# design.net
KiCad netlist of a schematic drawn in Altium Designer
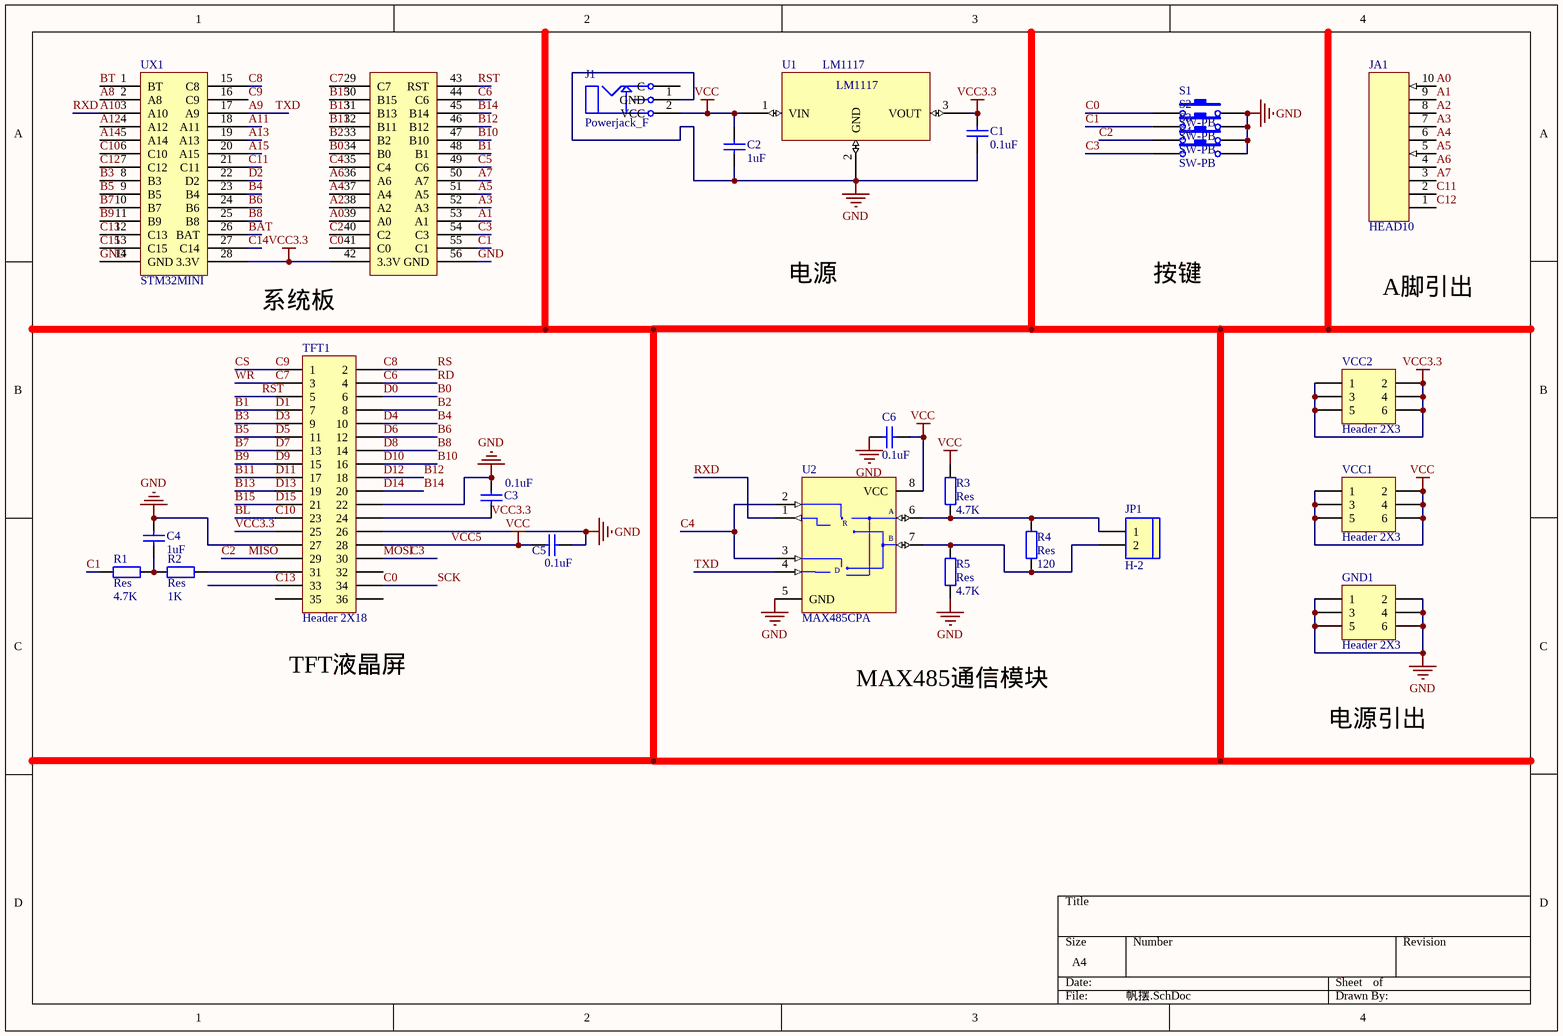
[diagram p0: 帆摆.SchDoc]

(export (version "E")
  (design (tool "Eeschema 10.0.6"))
  (components
    (comp (ref "C1")
      (value "0.1uF")
      (footprint "CC1005-0402")
      (description "Capacitor")
      (fields
        (field (name "MANUFACTURER") "Generic Components")
        (field (name "Comment") "CAP")
        (field (name "PUBLISHER") "Altium Hobart Technology Centre")
      )
      (libsource (lib "HGH") (part "CAP"))
    )
    (comp (ref "C2")
      (value "1uF")
      (footprint "CC1005-0402")
      (description "Capacitor")
      (fields
        (field (name "MANUFACTURER") "Generic Components")
        (field (name "Comment") "CAP")
        (field (name "PUBLISHER") "Altium Hobart Technology Centre")
      )
      (libsource (lib "HGH") (part "CAP"))
    )
    (comp (ref "C3")
      (value "0.1uF")
      (footprint "CC1005-0402")
      (description "Capacitor")
      (fields
        (field (name "MANUFACTURER") "Generic Components")
        (field (name "Comment") "CAP")
        (field (name "PUBLISHER") "Altium Hobart Technology Centre")
      )
      (libsource (lib "HGH - 副本") (part "CAP"))
    )
    (comp (ref "C4")
      (value "1uF")
      (footprint "CC1005-0402")
      (description "Capacitor")
      (fields
        (field (name "MANUFACTURER") "Generic Components")
        (field (name "Comment") "CAP")
        (field (name "PUBLISHER") "Altium Hobart Technology Centre")
      )
      (libsource (lib "HGH - 副本") (part "CAP"))
    )
    (comp (ref "C5")
      (value "0.1uF")
      (footprint "CC1005-0402")
      (description "Capacitor")
      (fields
        (field (name "MANUFACTURER") "Generic Components")
        (field (name "Comment") "CAP")
        (field (name "PUBLISHER") "Altium Hobart Technology Centre")
      )
      (libsource (lib "HGH - 副本") (part "CAP"))
    )
    (comp (ref "C6")
      (value "0.1uF")
      (footprint "CC1005-0402")
      (description "Capacitor")
      (fields
        (field (name "MANUFACTURER") "Generic Components")
        (field (name "Comment") "CAP")
        (field (name "PUBLISHER") "Altium Hobart Technology Centre")
      )
      (libsource (lib "HGH") (part "CAP"))
    )
    (comp (ref "GND1")
      (value "Header 2X3")
      (footprint "HDR2-3")
      (description "Header, 3-Pin, Dual row")
      (fields (field (name "MANUFACTURER") "Generic Components"))
      (libsource (lib "HGH") (part "Header 2X3"))
    )
    (comp (ref "J1")
      (value "Powerjack_F")
      (footprint "PWJ-2/3")
      (description "2-Conductor Jack with 1 break contact")
      (fields (field (name "MANUFACTURER") "Generic Components"))
      (libsource (lib "HGH") (part "Powerjack_F"))
    )
    (comp (ref "JA1")
      (value "HEAD10")
      (footprint "HEAD10M")
      (description "Connector,10-pin")
      (libsource (lib "HGH") (part "HEAD10"))
    )
    (comp (ref "JP1")
      (value "H-2")
      (footprint "H-2/2-T")
      (description "Header, 2-Pin")
      (fields (field (name "MANUFACTURER") "Generic Components"))
      (libsource (lib "HGH") (part "H-2"))
    )
    (comp (ref "R1")
      (value "Res")
      (footprint "R2012-0805")
      (description "Resistor")
      (fields
        (field (name "MANUFACTURER") "Generic Components")
        (field (name "ALTIUM_VALUE") "4.7K")
        (field (name "PUBLISHER") "Altium Hobart Technology Centre")
      )
      (libsource (lib "HGH - 副本") (part "Res"))
    )
    (comp (ref "R2")
      (value "Res")
      (footprint "R2012-0805")
      (description "Resistor")
      (fields
        (field (name "MANUFACTURER") "Generic Components")
        (field (name "ALTIUM_VALUE") "1K")
        (field (name "PUBLISHER") "Altium Hobart Technology Centre")
      )
      (libsource (lib "HGH - 副本") (part "Res"))
    )
    (comp (ref "R3")
      (value "Res")
      (footprint "R2012-0805")
      (description "Resistor")
      (fields
        (field (name "MANUFACTURER") "Generic Components")
        (field (name "ALTIUM_VALUE") "4.7K")
        (field (name "PUBLISHER") "Altium Hobart Technology Centre")
      )
      (libsource (lib "HGH") (part "Res"))
    )
    (comp (ref "R4")
      (value "Res")
      (footprint "R2012-0805")
      (description "Resistor")
      (fields
        (field (name "MANUFACTURER") "Generic Components")
        (field (name "ALTIUM_VALUE") "120")
        (field (name "PUBLISHER") "Altium Hobart Technology Centre")
      )
      (libsource (lib "HGH") (part "Res"))
    )
    (comp (ref "R5")
      (value "Res")
      (footprint "R2012-0805")
      (description "Resistor")
      (fields
        (field (name "MANUFACTURER") "Generic Components")
        (field (name "ALTIUM_VALUE") "4.7K")
        (field (name "PUBLISHER") "Altium Hobart Technology Centre")
      )
      (libsource (lib "HGH") (part "Res"))
    )
    (comp (ref "S1")
      (value "SW-PB")
      (footprint "SW-PB-4S")
      (description "Switch")
      (fields (field (name "MANUFACTURER") "Generic Components"))
      (libsource (lib "实验室") (part "SW-PB"))
    )
    (comp (ref "S2")
      (value "SW-PB")
      (footprint "SW-PB-4S")
      (description "Switch")
      (fields (field (name "MANUFACTURER") "Generic Components"))
      (libsource (lib "实验室") (part "SW-PB"))
    )
    (comp (ref "S3")
      (value "SW-PB")
      (footprint "SW-PB-4S")
      (description "Switch")
      (fields (field (name "MANUFACTURER") "Generic Components"))
      (libsource (lib "实验室") (part "SW-PB"))
    )
    (comp (ref "S4")
      (value "SW-PB")
      (footprint "SW-PB-4S")
      (description "Switch")
      (fields (field (name "MANUFACTURER") "Generic Components"))
      (libsource (lib "实验室") (part "SW-PB"))
    )
    (comp (ref "TFT1")
      (value "Header 2X18")
      (footprint "HDR2-18")
      (description "Header, 18Pin, Dual row")
      (fields (field (name "MANUFACTURER") "Generic Components"))
      (libsource (lib "HGH - 副本") (part "Header 2X18"))
    )
    (comp (ref "U1") (value "LM1117") (footprint "DSO-G3/P2.3") (libsource (lib "HGH") (part "LM1117")))
    (comp (ref "U2")
      (value "MAX485CPA")
      (footprint "DIP8")
      (description "Low-Power, Slew-Rate-Limited RS-485/RS-422 Transceiver")
      (fields
        (field (name "MANUFACTURER") "Maxim")
        (field (name "PUBLISHER") "Altium Hobart Technology Centre")
      )
      (libsource (lib "HGH") (part "MAX485CPA"))
    )
    (comp (ref "UX1")
      (value "STM32MINI")
      (footprint "STM32---MIN---64")
      (libsource (lib "HGH") (part "STM32---MIN--64"))
    )
    (comp (ref "VCC1")
      (value "Header 2X3")
      (footprint "HDR2-3")
      (description "Header, 3-Pin, Dual row")
      (fields (field (name "MANUFACTURER") "Generic Components"))
      (libsource (lib "HGH") (part "Header 2X3"))
    )
    (comp (ref "VCC2")
      (value "Header 2X3")
      (footprint "HDR2-3")
      (description "Header, 3-Pin, Dual row")
      (fields (field (name "MANUFACTURER") "Generic Components"))
      (libsource (lib "HGH") (part "Header 2X3"))
    )
  )
  (nets
    (net (code "2") (name "/A0") (class "Default")
      (node (ref "JA1") (pin "10") (pinfunction "10_10") (pintype "input"))
      (node (ref "UX1") (pin "39") (pinfunction "A0_39") (pintype "passive"))
    )
    (net (code "3") (name "/A1") (class "Default")
      (node (ref "JA1") (pin "9") (pinfunction "9_9") (pintype "passive"))
      (node (ref "UX1") (pin "53") (pinfunction "A1_53") (pintype "passive"))
    )
    (net (code "4") (name "/A2") (class "Default")
      (node (ref "JA1") (pin "8") (pinfunction "8_8") (pintype "passive"))
      (node (ref "UX1") (pin "38") (pinfunction "A2_38") (pintype "passive"))
    )
    (net (code "5") (name "/A3") (class "Default")
      (node (ref "JA1") (pin "7") (pinfunction "7_7") (pintype "passive"))
      (node (ref "UX1") (pin "52") (pinfunction "A3_52") (pintype "passive"))
    )
    (net (code "6") (name "/A4") (class "Default")
      (node (ref "JA1") (pin "6") (pinfunction "6_6") (pintype "passive"))
      (node (ref "UX1") (pin "37") (pinfunction "A4_37") (pintype "passive"))
    )
    (net (code "7") (name "/A5") (class "Default")
      (node (ref "JA1") (pin "5") (pinfunction "5_5") (pintype "input"))
      (node (ref "UX1") (pin "51") (pinfunction "A5_51") (pintype "passive"))
    )
    (net (code "8") (name "/A6") (class "Default")
      (node (ref "JA1") (pin "4") (pinfunction "4_4") (pintype "power_in"))
      (node (ref "UX1") (pin "36") (pinfunction "A6_36") (pintype "passive"))
    )
    (net (code "9") (name "/A7") (class "Default")
      (node (ref "JA1") (pin "3") (pinfunction "3_3") (pintype "power_in"))
      (node (ref "UX1") (pin "50") (pinfunction "A7_50") (pintype "passive"))
    )
    (net (code "10") (name "/A8") (class "Default")
      (node (ref "UX1") (pin "2") (pinfunction "A8_2") (pintype "passive"))
    )
    (net (code "11") (name "/A9") (class "Default")
      (node (ref "U2") (pin "4") (pinfunction "DI_4") (pintype "input"))
      (node (ref "UX1") (pin "17") (pinfunction "A9_17") (pintype "passive"))
    )
    (net (code "12") (name "/A10") (class "Default")
      (node (ref "U2") (pin "1") (pinfunction "RO_1") (pintype "output"))
      (node (ref "UX1") (pin "3") (pinfunction "A10_3") (pintype "passive"))
    )
    (net (code "13") (name "/A11") (class "Default")
      (node (ref "UX1") (pin "18") (pinfunction "A11_18") (pintype "passive"))
    )
    (net (code "14") (name "/A12") (class "Default")
      (node (ref "UX1") (pin "4") (pinfunction "A12_4") (pintype "passive"))
    )
    (net (code "15") (name "/A13") (class "Default")
      (node (ref "UX1") (pin "19") (pinfunction "A13_19") (pintype "passive"))
    )
    (net (code "16") (name "/A14") (class "Default")
      (node (ref "UX1") (pin "5") (pinfunction "A14_5") (pintype "passive"))
    )
    (net (code "17") (name "/A15") (class "Default")
      (node (ref "UX1") (pin "20") (pinfunction "A15_20") (pintype "passive"))
    )
    (net (code "20") (name "/B0") (class "Default")
      (node (ref "TFT1") (pin "6") (pinfunction "6_6") (pintype "passive"))
      (node (ref "UX1") (pin "34") (pinfunction "B0_34") (pintype "passive"))
    )
    (net (code "21") (name "/B1") (class "Default")
      (node (ref "TFT1") (pin "7") (pinfunction "7_7") (pintype "passive"))
      (node (ref "UX1") (pin "48") (pinfunction "B1_48") (pintype "passive"))
    )
    (net (code "22") (name "/B2") (class "Default")
      (node (ref "TFT1") (pin "8") (pinfunction "8_8") (pintype "passive"))
      (node (ref "UX1") (pin "33") (pinfunction "B2_33") (pintype "passive"))
    )
    (net (code "23") (name "/B3") (class "Default")
      (node (ref "TFT1") (pin "9") (pinfunction "9_9") (pintype "passive"))
      (node (ref "UX1") (pin "8") (pinfunction "B3_8") (pintype "passive"))
    )
    (net (code "24") (name "/B4") (class "Default")
      (node (ref "TFT1") (pin "10") (pinfunction "10_10") (pintype "passive"))
      (node (ref "UX1") (pin "23") (pinfunction "B4_23") (pintype "passive"))
    )
    (net (code "25") (name "/B5") (class "Default")
      (node (ref "TFT1") (pin "11") (pinfunction "11_11") (pintype "passive"))
      (node (ref "UX1") (pin "9") (pinfunction "B5_9") (pintype "passive"))
    )
    (net (code "26") (name "/B6") (class "Default")
      (node (ref "TFT1") (pin "12") (pinfunction "12_12") (pintype "passive"))
      (node (ref "UX1") (pin "24") (pinfunction "B6_24") (pintype "passive"))
    )
    (net (code "27") (name "/B7") (class "Default")
      (node (ref "TFT1") (pin "13") (pinfunction "13_13") (pintype "passive"))
      (node (ref "UX1") (pin "10") (pinfunction "B7_10") (pintype "passive"))
    )
    (net (code "28") (name "/B8") (class "Default")
      (node (ref "TFT1") (pin "14") (pinfunction "14_14") (pintype "passive"))
      (node (ref "UX1") (pin "25") (pinfunction "B8_25") (pintype "passive"))
    )
    (net (code "29") (name "/B9") (class "Default")
      (node (ref "TFT1") (pin "15") (pinfunction "15_15") (pintype "passive"))
      (node (ref "UX1") (pin "11") (pinfunction "B9_11") (pintype "passive"))
    )
    (net (code "30") (name "/B10") (class "Default")
      (node (ref "TFT1") (pin "16") (pinfunction "16_16") (pintype "passive"))
      (node (ref "UX1") (pin "47") (pinfunction "B10_47") (pintype "passive"))
    )
    (net (code "31") (name "/B11") (class "Default")
      (node (ref "TFT1") (pin "17") (pinfunction "17_17") (pintype "passive"))
      (node (ref "UX1") (pin "32") (pinfunction "B11_32") (pintype "passive"))
    )
    (net (code "32") (name "/B12") (class "Default")
      (node (ref "TFT1") (pin "18") (pinfunction "18_18") (pintype "passive"))
      (node (ref "UX1") (pin "46") (pinfunction "B12_46") (pintype "passive"))
    )
    (net (code "33") (name "/B13") (class "Default")
      (node (ref "TFT1") (pin "19") (pinfunction "19_19") (pintype "passive"))
      (node (ref "UX1") (pin "31") (pinfunction "B13_31") (pintype "passive"))
    )
    (net (code "34") (name "/B14") (class "Default")
      (node (ref "TFT1") (pin "20") (pinfunction "20_20") (pintype "passive"))
      (node (ref "UX1") (pin "45") (pinfunction "B14_45") (pintype "passive"))
    )
    (net (code "35") (name "/B15") (class "Default")
      (node (ref "TFT1") (pin "21") (pinfunction "21_21") (pintype "passive"))
      (node (ref "UX1") (pin "30") (pinfunction "B15_30") (pintype "passive"))
    )
    (net (code "36") (name "/BAT") (class "Default")
      (node (ref "UX1") (pin "26") (pinfunction "BAT_26") (pintype "passive"))
    )
    (net (code "37") (name "/BL") (class "Default")
      (node (ref "TFT1") (pin "23") (pinfunction "23_23") (pintype "passive"))
      (node (ref "UX1") (pin "6") (pinfunction "C10_6") (pintype "passive"))
    )
    (net (code "38") (name "/BT") (class "Default")
      (node (ref "UX1") (pin "1") (pinfunction "BT_1") (pintype "passive"))
    )
    (net (code "39") (name "/C0") (class "Default")
      (node (ref "S1") (pin "1") (pinfunction "1_1") (pintype "passive"))
      (node (ref "TFT1") (pin "34") (pinfunction "34_34") (pintype "passive"))
      (node (ref "UX1") (pin "41") (pinfunction "C0_41") (pintype "passive"))
    )
    (net (code "40") (name "/C1") (class "Default")
      (node (ref "R1") (pin "1") (pinfunction "1_1") (pintype "passive"))
      (node (ref "S2") (pin "1") (pinfunction "1_1") (pintype "passive"))
      (node (ref "UX1") (pin "55") (pinfunction "C1_55") (pintype "passive"))
    )
    (net (code "41") (name "/C2") (class "Default")
      (node (ref "S3") (pin "1") (pinfunction "1_1") (pintype "passive"))
      (node (ref "TFT1") (pin "29") (pinfunction "29_29") (pintype "passive"))
      (node (ref "UX1") (pin "40") (pinfunction "C2_40") (pintype "passive"))
    )
    (net (code "42") (name "/C3") (class "Default")
      (node (ref "S4") (pin "1") (pinfunction "1_1") (pintype "passive"))
      (node (ref "TFT1") (pin "30") (pinfunction "30_30") (pintype "passive"))
      (node (ref "UX1") (pin "54") (pinfunction "C3_54") (pintype "passive"))
    )
    (net (code "43") (name "/C4") (class "Default")
      (node (ref "U2") (pin "2") (pinfunction "~{RE}_2") (pintype "input"))
      (node (ref "U2") (pin "3") (pinfunction "DE_3") (pintype "input"))
      (node (ref "UX1") (pin "35") (pinfunction "C4_35") (pintype "passive"))
    )
    (net (code "44") (name "/C5") (class "Default")
      (node (ref "UX1") (pin "49") (pinfunction "C6_49") (pintype "passive"))
    )
    (net (code "45") (name "/C6") (class "Default")
      (node (ref "TFT1") (pin "4") (pinfunction "4_4") (pintype "passive"))
      (node (ref "UX1") (pin "44") (pinfunction "C6_44") (pintype "passive"))
    )
    (net (code "46") (name "/C7") (class "Default")
      (node (ref "TFT1") (pin "3") (pinfunction "3_3") (pintype "passive"))
      (node (ref "UX1") (pin "29") (pinfunction "C7_29") (pintype "passive"))
    )
    (net (code "47") (name "/C8") (class "Default")
      (node (ref "TFT1") (pin "2") (pinfunction "2_2") (pintype "passive"))
      (node (ref "UX1") (pin "15") (pinfunction "C8_15") (pintype "passive"))
    )
    (net (code "48") (name "/C9") (class "Default")
      (node (ref "TFT1") (pin "1") (pinfunction "1_1") (pintype "passive"))
      (node (ref "UX1") (pin "16") (pinfunction "C9_16") (pintype "passive"))
    )
    (net (code "49") (name "/C11") (class "Default")
      (node (ref "JA1") (pin "2") (pinfunction "2_2") (pintype "passive"))
      (node (ref "UX1") (pin "21") (pinfunction "C11_21") (pintype "passive"))
    )
    (net (code "50") (name "/C12") (class "Default")
      (node (ref "JA1") (pin "1") (pinfunction "1_1") (pintype "passive"))
      (node (ref "UX1") (pin "7") (pinfunction "C12_7") (pintype "passive"))
    )
    (net (code "51") (name "/C13") (class "Default")
      (node (ref "TFT1") (pin "33") (pinfunction "33_33") (pintype "passive"))
      (node (ref "UX1") (pin "12") (pinfunction "C13_12") (pintype "passive"))
    )
    (net (code "52") (name "/C14") (class "Default")
      (node (ref "UX1") (pin "27") (pinfunction "C14_27") (pintype "passive"))
    )
    (net (code "53") (name "/C15") (class "Default")
      (node (ref "UX1") (pin "13") (pinfunction "C15_13") (pintype "passive"))
    )
    (net (code "54") (name "/D2") (class "Default")
      (node (ref "UX1") (pin "22") (pinfunction "D2_22") (pintype "passive"))
    )
    (net (code "56") (name "/RST") (class "Default")
      (node (ref "TFT1") (pin "5") (pinfunction "5_5") (pintype "passive"))
      (node (ref "UX1") (pin "43") (pinfunction "RST_43") (pintype "passive"))
    )
    (net (code "62") (name "GND") (class "Default")
      (node (ref "C1") (pin "1") (pinfunction "1_1") (pintype "passive"))
      (node (ref "C2") (pin "1") (pinfunction "1_1") (pintype "passive"))
      (node (ref "C3") (pin "2") (pinfunction "2_2") (pintype "passive"))
      (node (ref "C4") (pin "2") (pinfunction "2_2") (pintype "passive"))
      (node (ref "C5") (pin "1") (pinfunction "1_1") (pintype "passive"))
      (node (ref "C6") (pin "1") (pinfunction "1_1") (pintype "passive"))
      (node (ref "GND1") (pin "1") (pinfunction "1_1") (pintype "passive"))
      (node (ref "GND1") (pin "2") (pinfunction "2_2") (pintype "passive"))
      (node (ref "GND1") (pin "3") (pinfunction "3_3") (pintype "passive"))
      (node (ref "GND1") (pin "4") (pinfunction "4_4") (pintype "passive"))
      (node (ref "GND1") (pin "5") (pinfunction "5_5") (pintype "passive"))
      (node (ref "GND1") (pin "6") (pinfunction "6_6") (pintype "passive"))
      (node (ref "J1") (pin "1") (pinfunction "GND_1") (pintype "passive"))
      (node (ref "R5") (pin "1") (pinfunction "1_1") (pintype "passive"))
      (node (ref "S1") (pin "2") (pinfunction "2_2") (pintype "passive"))
      (node (ref "S2") (pin "2") (pinfunction "2_2") (pintype "passive"))
      (node (ref "S3") (pin "2") (pinfunction "2_2") (pintype "passive"))
      (node (ref "S4") (pin "2") (pinfunction "2_2") (pintype "passive"))
      (node (ref "TFT1") (pin "22") (pinfunction "22_22") (pintype "passive"))
      (node (ref "TFT1") (pin "26") (pinfunction "26_26") (pintype "passive"))
      (node (ref "TFT1") (pin "27") (pinfunction "27_27") (pintype "passive"))
      (node (ref "U1") (pin "2") (pinfunction "GND_2") (pintype "bidirectional"))
      (node (ref "U2") (pin "5") (pinfunction "GND_5") (pintype "power_in"))
      (node (ref "UX1") (pin "14") (pinfunction "GND_14") (pintype "passive"))
      (node (ref "UX1") (pin "56") (pinfunction "GND_56") (pintype "passive"))
    )
    (net (code "63") (name "Net-(C4-Pad1)") (class "Default")
      (node (ref "C4") (pin "1") (pinfunction "1_1") (pintype "passive"))
      (node (ref "R1") (pin "2") (pinfunction "2_2") (pintype "passive"))
      (node (ref "R2") (pin "1") (pinfunction "1_1") (pintype "passive"))
    )
    (net (code "64") (name "Net-(R2-Pad2)") (class "Default")
      (node (ref "R2") (pin "2") (pinfunction "2_2") (pintype "passive"))
      (node (ref "TFT1") (pin "31") (pinfunction "31_31") (pintype "passive"))
    )
    (net (code "65") (name "Net-(U2-A)") (class "Default")
      (node (ref "JP1") (pin "1") (pinfunction "1_1") (pintype "passive"))
      (node (ref "R3") (pin "1") (pinfunction "1_1") (pintype "passive"))
      (node (ref "R4") (pin "2") (pinfunction "2_2") (pintype "passive"))
      (node (ref "U2") (pin "6") (pinfunction "A_6") (pintype "bidirectional"))
    )
    (net (code "66") (name "Net-(U2-B)") (class "Default")
      (node (ref "JP1") (pin "2") (pinfunction "2_2") (pintype "passive"))
      (node (ref "R4") (pin "1") (pinfunction "1_1") (pintype "passive"))
      (node (ref "R5") (pin "2") (pinfunction "2_2") (pintype "passive"))
      (node (ref "U2") (pin "7") (pinfunction "B_7") (pintype "bidirectional"))
    )
    (net (code "67") (name "VCC") (class "Default")
      (node (ref "C2") (pin "2") (pinfunction "2_2") (pintype "passive"))
      (node (ref "C5") (pin "2") (pinfunction "2_2") (pintype "passive"))
      (node (ref "C6") (pin "2") (pinfunction "2_2") (pintype "passive"))
      (node (ref "J1") (pin "2") (pinfunction "VCC_2") (pintype "passive"))
      (node (ref "R3") (pin "2") (pinfunction "2_2") (pintype "passive"))
      (node (ref "TFT1") (pin "28") (pinfunction "28_28") (pintype "passive"))
      (node (ref "U1") (pin "1") (pinfunction "VIN_1") (pintype "bidirectional"))
      (node (ref "U2") (pin "8") (pinfunction "VCC_8") (pintype "power_in"))
      (node (ref "VCC1") (pin "1") (pinfunction "1_1") (pintype "passive"))
      (node (ref "VCC1") (pin "2") (pinfunction "2_2") (pintype "passive"))
      (node (ref "VCC1") (pin "3") (pinfunction "3_3") (pintype "passive"))
      (node (ref "VCC1") (pin "4") (pinfunction "4_4") (pintype "passive"))
      (node (ref "VCC1") (pin "5") (pinfunction "5_5") (pintype "passive"))
      (node (ref "VCC1") (pin "6") (pinfunction "6_6") (pintype "passive"))
    )
    (net (code "68") (name "VCC3.3") (class "Default")
      (node (ref "C1") (pin "2") (pinfunction "2_2") (pintype "passive"))
      (node (ref "C3") (pin "1") (pinfunction "1_1") (pintype "passive"))
      (node (ref "TFT1") (pin "24") (pinfunction "24_24") (pintype "passive"))
      (node (ref "TFT1") (pin "25") (pinfunction "25_25") (pintype "passive"))
      (node (ref "U1") (pin "3") (pinfunction "VOUT_3") (pintype "bidirectional"))
      (node (ref "UX1") (pin "28") (pinfunction "3.3V_28") (pintype "passive"))
      (node (ref "UX1") (pin "42") (pinfunction "3.3V_42") (pintype "passive"))
      (node (ref "VCC2") (pin "1") (pinfunction "1_1") (pintype "passive"))
      (node (ref "VCC2") (pin "2") (pinfunction "2_2") (pintype "passive"))
      (node (ref "VCC2") (pin "3") (pinfunction "3_3") (pintype "passive"))
      (node (ref "VCC2") (pin "4") (pinfunction "4_4") (pintype "passive"))
      (node (ref "VCC2") (pin "5") (pinfunction "5_5") (pintype "passive"))
      (node (ref "VCC2") (pin "6") (pinfunction "6_6") (pintype "passive"))
    )
    (net (code "69") (name "unconnected-(J1-C-Pad3)") (class "Default")
      (node (ref "J1") (pin "3") (pinfunction "C_3") (pintype "passive"))
    )
    (net (code "70") (name "unconnected-(TFT1-Pad32)") (class "Default")
      (node (ref "TFT1") (pin "32") (pinfunction "32_32") (pintype "passive"))
    )
    (net (code "71") (name "unconnected-(TFT1-Pad35)") (class "Default")
      (node (ref "TFT1") (pin "35") (pinfunction "35_35") (pintype "passive"))
    )
    (net (code "72") (name "unconnected-(TFT1-Pad36)") (class "Default")
      (node (ref "TFT1") (pin "36") (pinfunction "36_36") (pintype "passive"))
    )
  )
)
